# LIFT_CARD.net
KiCad netlist of a schematic drawn in Altium Designer
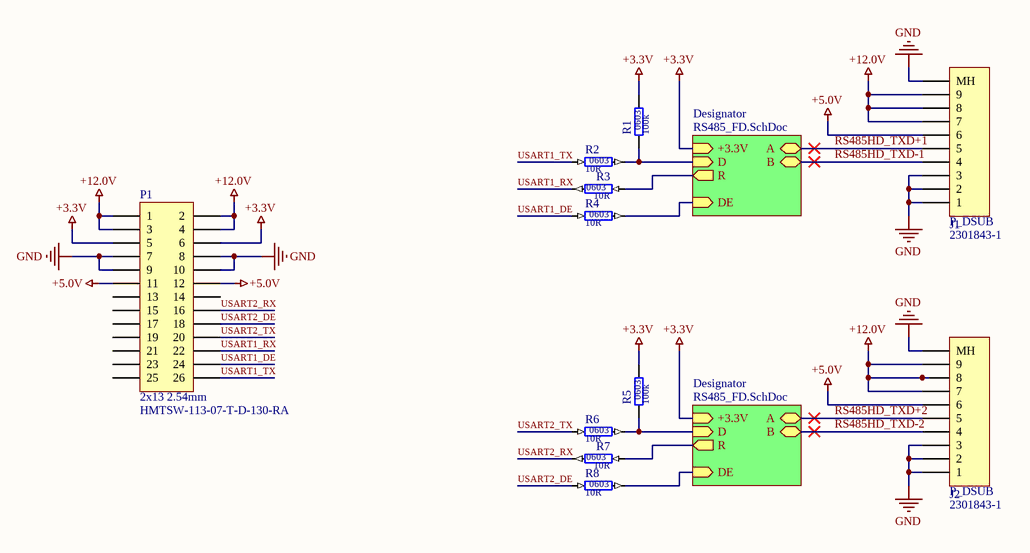
[diagram p0: LIFT_CARD.SchDoc]

(export (version "E")
  (design (tool "Eeschema 10.0.6"))
  (components
    (comp (ref "J1")
      (value "2301843-1")
      (footprint "P_DSUB_2301843-1")
      (description "Header, 9-Pin")
      (fields
        (field (name "SCH_FOOTPRINT") "P_DSUB")
        (field (name "PART NUMBER") "P_DSUB_2301843-1")
        (field (name "MANUFACTURER") "TE Conectivity")
      )
      (libsource (lib "Library") (part "J_DSUB"))
    )
    (comp (ref "J2")
      (value "2301843-1")
      (footprint "P_DSUB_2301843-1")
      (description "Header, 9-Pin")
      (fields
        (field (name "SCH_FOOTPRINT") "P_DSUB")
        (field (name "PART NUMBER") "P_DSUB_2301843-1")
        (field (name "MANUFACTURER") "TE Conectivity")
      )
      (libsource (lib "Library") (part "J_DSUB"))
    )
    (comp (ref "P1")
      (value "HMTSW-113-07-T-D-130-RA")
      (footprint "P_HEADER_2x13_2.54_RIGHT_ANGLE")
      (description "Pin Header")
      (fields
        (field (name "SCH_FOOTPRINT") "2x13 2.54mm")
        (field (name "PART NUMBER") "P_HEADER_2x13_2.54_ANGLE")
        (field (name "MANUFACTURER") "Samtec")
      )
      (libsource (lib "Library") (part "P_HEADER_2x13"))
    )
    (comp (ref "R1")
      (value "100k")
      (footprint "R_0603_1608")
      (fields
        (field (name "SCH_FOOTPRINT") "0603")
        (field (name "PART NUMBER") "R_100k_0603_1")
        (field (name "VOLTAGE") "50V")
        (field (name "POWER") "100mW")
      )
      (libsource (lib "") (part "R_1"))
    )
    (comp (ref "R2")
      (value "10R")
      (footprint "R_0603_1608")
      (fields
        (field (name "SCH_FOOTPRINT") "0603")
        (field (name "PART NUMBER") "R_10R_0603_1")
        (field (name "VOLTAGE") "50V")
        (field (name "POWER") "100mW")
      )
      (libsource (lib "Library") (part "R"))
    )
    (comp (ref "R3")
      (value "10R")
      (footprint "R_0603_1608")
      (fields
        (field (name "SCH_FOOTPRINT") "0603")
        (field (name "PART NUMBER") "R_10R_0603_1")
        (field (name "VOLTAGE") "50V")
        (field (name "POWER") "100mW")
      )
      (libsource (lib "Library") (part "R"))
    )
    (comp (ref "R4")
      (value "10R")
      (footprint "R_0603_1608")
      (fields
        (field (name "SCH_FOOTPRINT") "0603")
        (field (name "PART NUMBER") "R_10R_0603_1")
        (field (name "VOLTAGE") "50V")
        (field (name "POWER") "100mW")
      )
      (libsource (lib "Library") (part "R"))
    )
    (comp (ref "R5")
      (value "100k")
      (footprint "R_0603_1608")
      (fields
        (field (name "SCH_FOOTPRINT") "0603")
        (field (name "PART NUMBER") "R_100k_0603_1")
        (field (name "VOLTAGE") "50V")
        (field (name "POWER") "100mW")
      )
      (libsource (lib "") (part "R_1"))
    )
    (comp (ref "R6")
      (value "10R")
      (footprint "R_0603_1608")
      (fields
        (field (name "SCH_FOOTPRINT") "0603")
        (field (name "PART NUMBER") "R_10R_0603_1")
        (field (name "VOLTAGE") "50V")
        (field (name "POWER") "100mW")
      )
      (libsource (lib "Library") (part "R"))
    )
    (comp (ref "R7")
      (value "10R")
      (footprint "R_0603_1608")
      (fields
        (field (name "SCH_FOOTPRINT") "0603")
        (field (name "PART NUMBER") "R_10R_0603_1")
        (field (name "VOLTAGE") "50V")
        (field (name "POWER") "100mW")
      )
      (libsource (lib "Library") (part "R"))
    )
    (comp (ref "R8")
      (value "10R")
      (footprint "R_0603_1608")
      (fields
        (field (name "SCH_FOOTPRINT") "0603")
        (field (name "PART NUMBER") "R_10R_0603_1")
        (field (name "VOLTAGE") "50V")
        (field (name "POWER") "100mW")
      )
      (libsource (lib "Library") (part "R"))
    )
  )
  (nets
    (net (code "1") (name "+3.3V") (class "Default")
      (node (ref "P1") (pin "5") (pinfunction "5_5") (pintype "passive"))
      (node (ref "P1") (pin "6") (pinfunction "6_6") (pintype "passive"))
      (node (ref "R1") (pin "2") (pinfunction "2_2") (pintype "passive"))
      (node (ref "R5") (pin "2") (pinfunction "2_2") (pintype "passive"))
    )
    (net (code "2") (name "+5.0V") (class "Default")
      (node (ref "J1") (pin "6") (pinfunction "6_6") (pintype "passive"))
      (node (ref "J2") (pin "6") (pinfunction "6_6") (pintype "passive"))
      (node (ref "P1") (pin "11") (pinfunction "11_11") (pintype "passive"))
      (node (ref "P1") (pin "12") (pinfunction "12_12") (pintype "passive"))
    )
    (net (code "3") (name "+12.0V") (class "Default")
      (node (ref "J1") (pin "7") (pinfunction "7_7") (pintype "passive"))
      (node (ref "J1") (pin "8") (pinfunction "8_8") (pintype "passive"))
      (node (ref "J1") (pin "9") (pinfunction "9_9") (pintype "passive"))
      (node (ref "J2") (pin "7") (pinfunction "7_7") (pintype "passive"))
      (node (ref "J2") (pin "8") (pinfunction "8_8") (pintype "passive"))
      (node (ref "J2") (pin "9") (pinfunction "9_9") (pintype "passive"))
      (node (ref "P1") (pin "1") (pinfunction "1_1") (pintype "passive"))
      (node (ref "P1") (pin "2") (pinfunction "2_2") (pintype "passive"))
      (node (ref "P1") (pin "3") (pinfunction "3_3") (pintype "passive"))
      (node (ref "P1") (pin "4") (pinfunction "4_4") (pintype "passive"))
    )
    (net (code "4") (name "/D") (class "Default")
      (node (ref "R5") (pin "1") (pinfunction "1_1") (pintype "passive"))
      (node (ref "R6") (pin "2") (pinfunction "2_2") (pintype "output"))
    )
    (net (code "5") (name "/DE") (class "Default")
      (node (ref "R8") (pin "2") (pinfunction "2_2") (pintype "output"))
    )
    (net (code "6") (name "/DE_1") (class "Default")
      (node (ref "R4") (pin "2") (pinfunction "2_2") (pintype "output"))
    )
    (net (code "7") (name "/D_1") (class "Default")
      (node (ref "R1") (pin "1") (pinfunction "1_1") (pintype "passive"))
      (node (ref "R2") (pin "2") (pinfunction "2_2") (pintype "output"))
    )
    (net (code "8") (name "/R") (class "Default")
      (node (ref "R7") (pin "1") (pinfunction "1_1") (pintype "input"))
    )
    (net (code "9") (name "/RS485HD_TXD+1") (class "Default")
      (node (ref "J1") (pin "5") (pinfunction "5_5") (pintype "passive"))
    )
    (net (code "10") (name "/RS485HD_TXD+2") (class "Default")
      (node (ref "J2") (pin "5") (pinfunction "5_5") (pintype "passive"))
    )
    (net (code "11") (name "/RS485HD_TXD-1") (class "Default")
      (node (ref "J1") (pin "4") (pinfunction "4_4") (pintype "passive"))
    )
    (net (code "12") (name "/RS485HD_TXD-2") (class "Default")
      (node (ref "J2") (pin "4") (pinfunction "4_4") (pintype "passive"))
    )
    (net (code "13") (name "/R_1") (class "Default")
      (node (ref "R3") (pin "1") (pinfunction "1_1") (pintype "input"))
    )
    (net (code "14") (name "/USART1_DE") (class "Default")
      (node (ref "P1") (pin "24") (pinfunction "24_24") (pintype "passive"))
      (node (ref "R4") (pin "1") (pinfunction "1_1") (pintype "input"))
    )
    (net (code "15") (name "/USART1_RX") (class "Default")
      (node (ref "P1") (pin "22") (pinfunction "22_22") (pintype "passive"))
      (node (ref "R3") (pin "2") (pinfunction "2_2") (pintype "output"))
    )
    (net (code "16") (name "/USART1_TX") (class "Default")
      (node (ref "P1") (pin "26") (pinfunction "26_26") (pintype "passive"))
      (node (ref "R2") (pin "1") (pinfunction "1_1") (pintype "input"))
    )
    (net (code "17") (name "/USART2_DE") (class "Default")
      (node (ref "P1") (pin "18") (pinfunction "18_18") (pintype "passive"))
      (node (ref "R8") (pin "1") (pinfunction "1_1") (pintype "input"))
    )
    (net (code "18") (name "/USART2_RX") (class "Default")
      (node (ref "P1") (pin "16") (pinfunction "16_16") (pintype "passive"))
      (node (ref "R7") (pin "2") (pinfunction "2_2") (pintype "output"))
    )
    (net (code "19") (name "/USART2_TX") (class "Default")
      (node (ref "P1") (pin "20") (pinfunction "20_20") (pintype "passive"))
      (node (ref "R6") (pin "1") (pinfunction "1_1") (pintype "input"))
    )
    (net (code "20") (name "GND") (class "Default")
      (node (ref "J1") (pin "1") (pinfunction "1_1") (pintype "passive"))
      (node (ref "J1") (pin "2") (pinfunction "2_2") (pintype "passive"))
      (node (ref "J1") (pin "3") (pinfunction "3_3") (pintype "passive"))
      (node (ref "J1") (pin "MH") (pinfunction "MH_MH") (pintype "passive"))
      (node (ref "J2") (pin "1") (pinfunction "1_1") (pintype "passive"))
      (node (ref "J2") (pin "2") (pinfunction "2_2") (pintype "passive"))
      (node (ref "J2") (pin "3") (pinfunction "3_3") (pintype "passive"))
      (node (ref "J2") (pin "MH") (pinfunction "MH_MH") (pintype "passive"))
      (node (ref "P1") (pin "10") (pinfunction "10_10") (pintype "passive"))
      (node (ref "P1") (pin "7") (pinfunction "7_7") (pintype "passive"))
      (node (ref "P1") (pin "8") (pinfunction "8_8") (pintype "passive"))
      (node (ref "P1") (pin "9") (pinfunction "9_9") (pintype "passive"))
    )
    (net (code "21") (name "unconnected-(P1-Pad13)") (class "Default")
      (node (ref "P1") (pin "13") (pinfunction "13_13") (pintype "passive"))
    )
    (net (code "22") (name "unconnected-(P1-Pad14)") (class "Default")
      (node (ref "P1") (pin "14") (pinfunction "14_14") (pintype "passive"))
    )
    (net (code "23") (name "unconnected-(P1-Pad15)") (class "Default")
      (node (ref "P1") (pin "15") (pinfunction "15_15") (pintype "passive"))
    )
    (net (code "24") (name "unconnected-(P1-Pad17)") (class "Default")
      (node (ref "P1") (pin "17") (pinfunction "17_17") (pintype "passive"))
    )
    (net (code "25") (name "unconnected-(P1-Pad19)") (class "Default")
      (node (ref "P1") (pin "19") (pinfunction "19_19") (pintype "passive"))
    )
    (net (code "26") (name "unconnected-(P1-Pad21)") (class "Default")
      (node (ref "P1") (pin "21") (pinfunction "21_21") (pintype "passive"))
    )
    (net (code "27") (name "unconnected-(P1-Pad23)") (class "Default")
      (node (ref "P1") (pin "23") (pinfunction "23_23") (pintype "passive"))
    )
    (net (code "28") (name "unconnected-(P1-Pad25)") (class "Default")
      (node (ref "P1") (pin "25") (pinfunction "25_25") (pintype "passive"))
    )
  )
)
